# PROC054D_AWR_1_AWR_4_LC_Filtering.net
KiCad netlist of a schematic drawn in Altium Designer
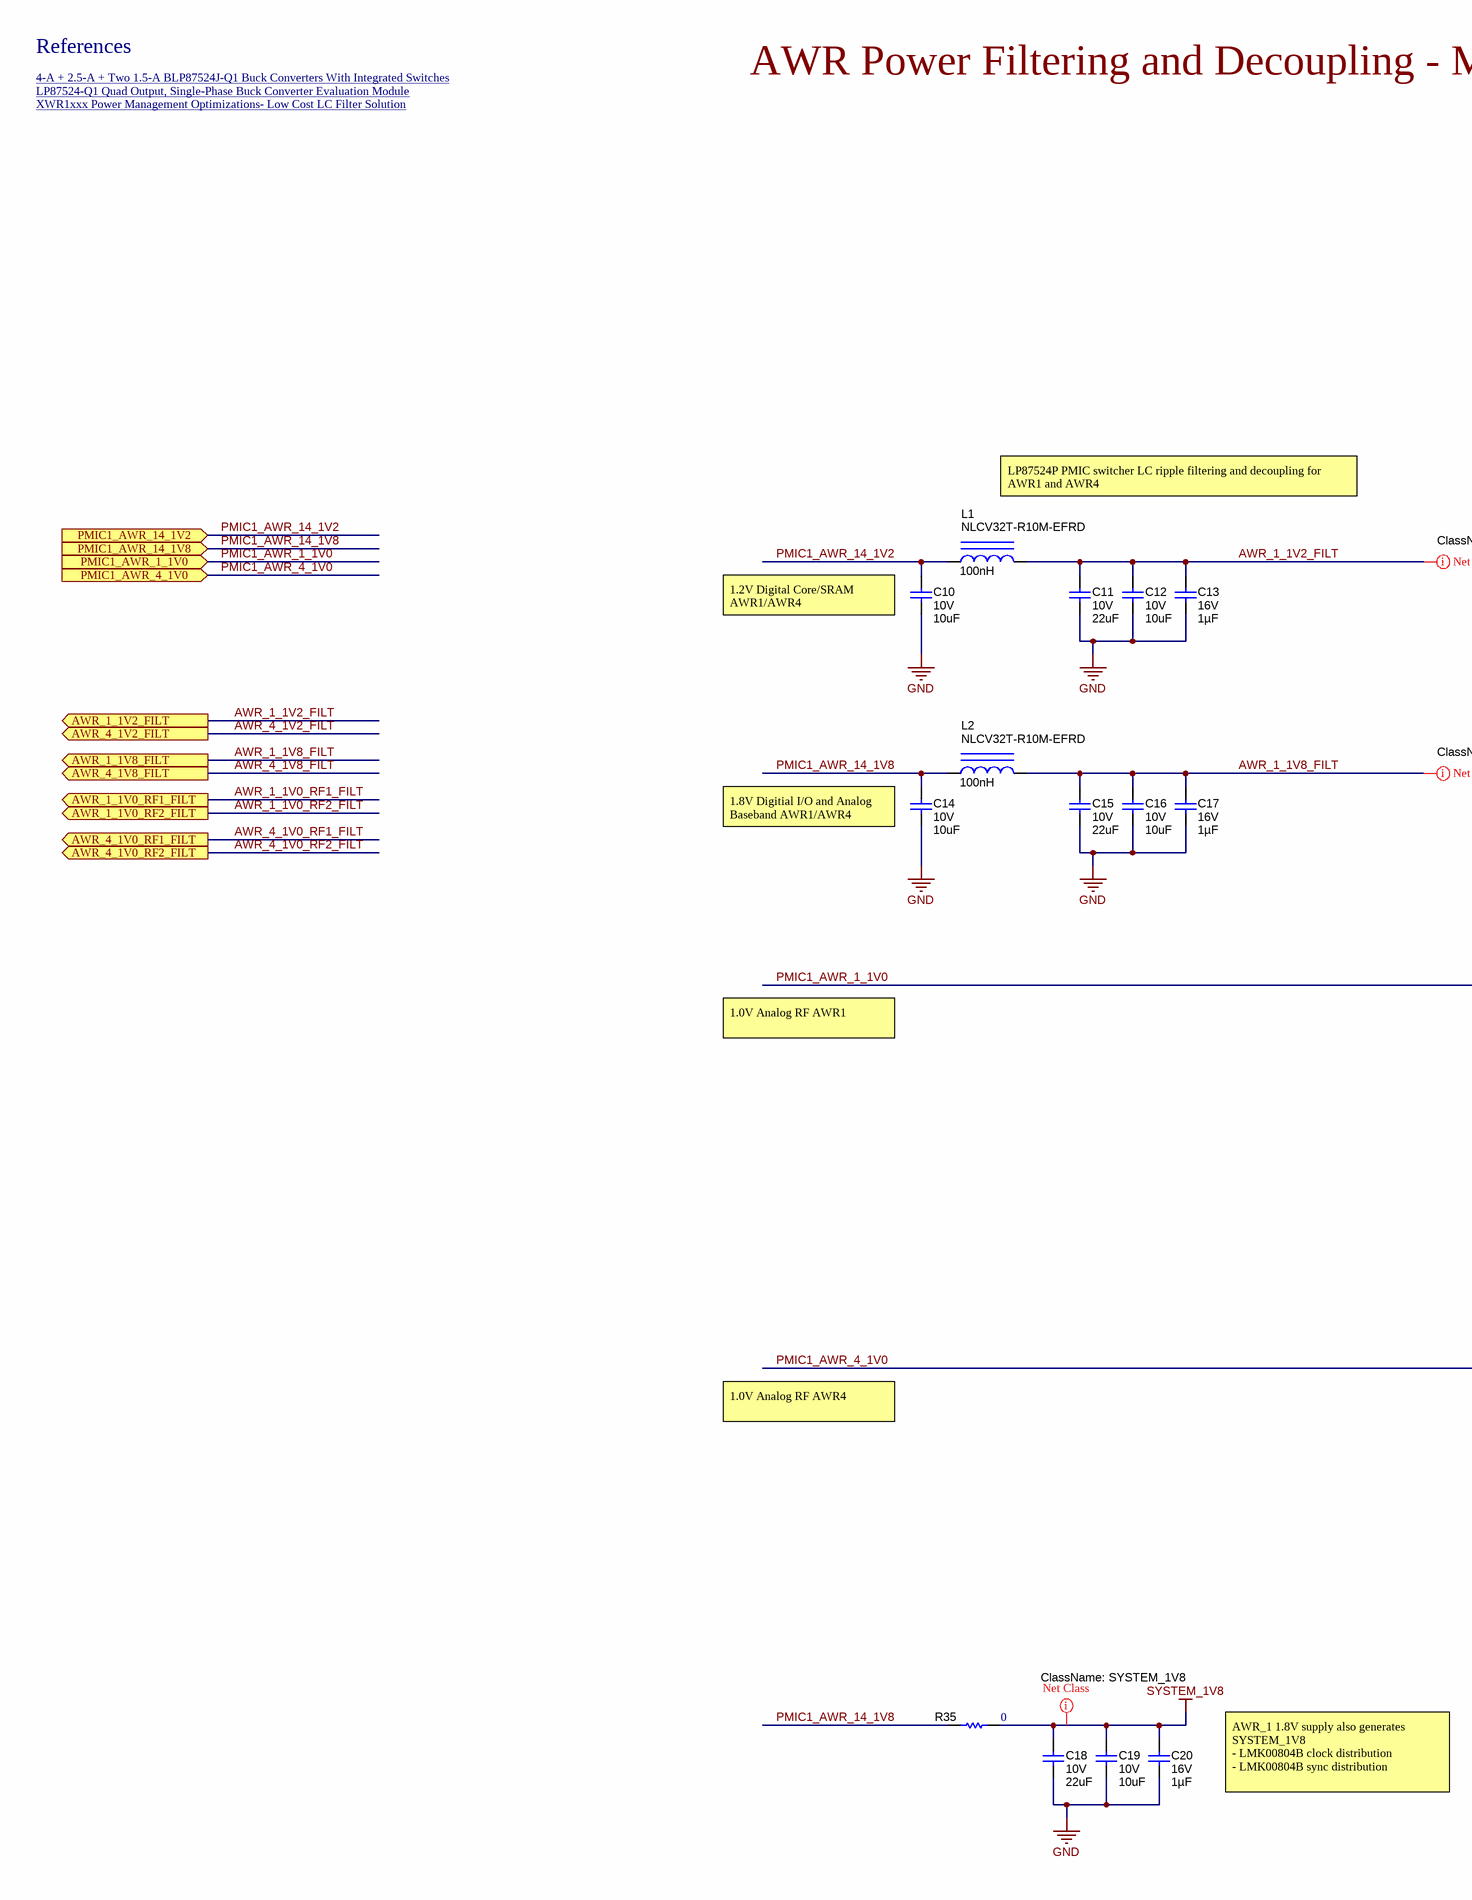
[diagram p0: PROC054D_AWR_1_AWR_4_LC_Filtering.SchDoc, left]
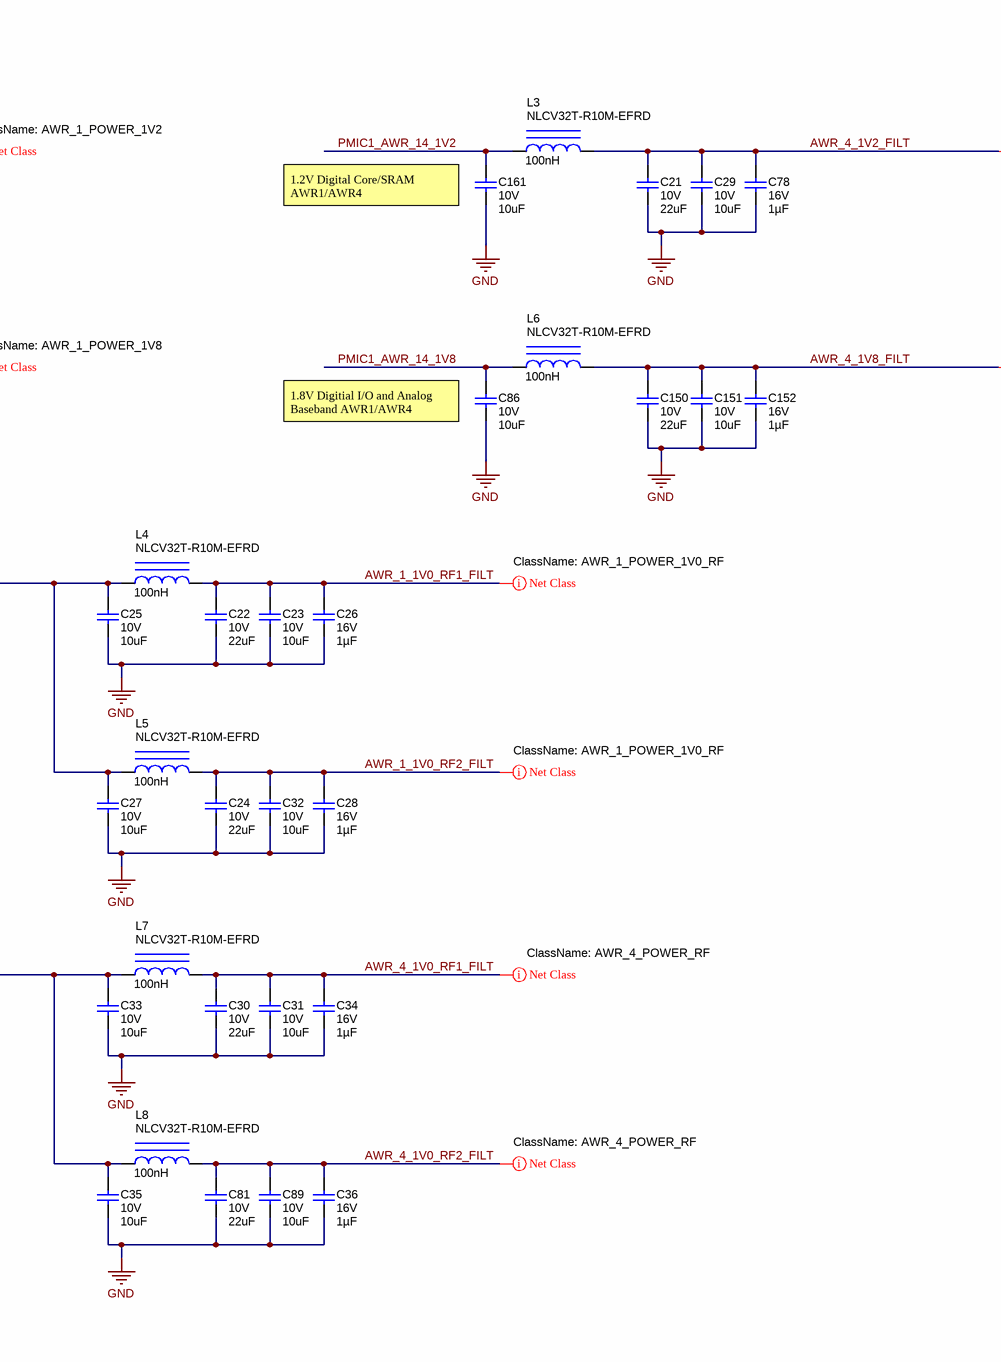
[diagram p1: PROC054D_AWR_1_AWR_4_LC_Filtering.SchDoc, right]

(export (version "E")
  (design (tool "Eeschema 10.0.6"))
  (components
    (comp (ref "C10")
      (value "GCM21BR71A106KE22L")
      (footprint "0805L")
      (description "CAP, CERM, 10 uF, 10 V, +/- 10%, X7R, 0805")
      (fields
        (field (name "MANUFACTURER") "MuRata")
        (field (name "VDC_V") "10V")
        (field (name "VALUEDISPLAYED") "10uF")
        (field (name "PUBLISHER") "Texas Instruments")
      )
      (libsource (lib "Altium Vault - TI") (part "Capacitor"))
    )
    (comp (ref "C11")
      (value "GCM31CR71A226KE02")
      (footprint "1206_180L")
      (description "CAP, CERM, 22 uF, 10 V, +/- 10%, X7R, AEC-Q200 Grade 1, 1206")
      (fields
        (field (name "MANUFACTURER") "MuRata")
        (field (name "VDC_V") "10V")
        (field (name "VALUEDISPLAYED") "22uF")
        (field (name "PUBLISHER") "Texas Instruments")
      )
      (libsource (lib "Altium Vault - TI") (part "CMP-0008811-2"))
    )
    (comp (ref "C12")
      (value "GCM21BR71A106KE22L")
      (footprint "0805L")
      (description "CAP, CERM, 10 uF, 10 V, +/- 10%, X7R, 0805")
      (fields
        (field (name "MANUFACTURER") "MuRata")
        (field (name "VDC_V") "10V")
        (field (name "VALUEDISPLAYED") "10uF")
        (field (name "PUBLISHER") "Texas Instruments")
      )
      (libsource (lib "Altium Vault - TI") (part "Capacitor"))
    )
    (comp (ref "C13")
      (value "GCM188R71C105KA64J")
      (footprint "0603S")
      (description "CAP, CERM, 1 µF, 16 V,+/- 10%, X7R, AEC-Q200 Grade 1, 0603")
      (fields
        (field (name "MANUFACTURER") "MuRata")
        (field (name "VDC_V") "16V")
        (field (name "VALUEDISPLAYED") "1µF")
      )
      (libsource (lib "Altium Vault - TI") (part "Capacitor"))
    )
    (comp (ref "C14")
      (value "GCM21BR71A106KE22L")
      (footprint "0805L")
      (description "CAP, CERM, 10 uF, 10 V, +/- 10%, X7R, 0805")
      (fields
        (field (name "MANUFACTURER") "MuRata")
        (field (name "VDC_V") "10V")
        (field (name "VALUEDISPLAYED") "10uF")
        (field (name "PUBLISHER") "Texas Instruments")
      )
      (libsource (lib "Altium Vault - TI") (part "Capacitor"))
    )
    (comp (ref "C15")
      (value "GCM31CR71A226KE02")
      (footprint "1206_180L")
      (description "CAP, CERM, 22 uF, 10 V, +/- 10%, X7R, AEC-Q200 Grade 1, 1206")
      (fields
        (field (name "MANUFACTURER") "MuRata")
        (field (name "VDC_V") "10V")
        (field (name "VALUEDISPLAYED") "22uF")
        (field (name "PUBLISHER") "Texas Instruments")
      )
      (libsource (lib "Altium Vault - TI") (part "Capacitor"))
    )
    (comp (ref "C16")
      (value "GCM21BR71A106KE22L")
      (footprint "0805L")
      (description "CAP, CERM, 10 uF, 10 V, +/- 10%, X7R, 0805")
      (fields
        (field (name "MANUFACTURER") "MuRata")
        (field (name "VDC_V") "10V")
        (field (name "VALUEDISPLAYED") "10uF")
        (field (name "PUBLISHER") "Texas Instruments")
      )
      (libsource (lib "Altium Vault - TI") (part "Capacitor"))
    )
    (comp (ref "C17")
      (value "GCM188R71C105KA64J")
      (footprint "0603S")
      (description "CAP, CERM, 1 µF, 16 V,+/- 10%, X7R, AEC-Q200 Grade 1, 0603")
      (fields
        (field (name "MANUFACTURER") "MuRata")
        (field (name "VDC_V") "16V")
        (field (name "VALUEDISPLAYED") "1µF")
      )
      (libsource (lib "Altium Vault - TI") (part "Capacitor"))
    )
    (comp (ref "C18")
      (value "GCM31CR71A226KE02")
      (footprint "1206_180L")
      (description "CAP, CERM, 22 uF, 10 V, +/- 10%, X7R, AEC-Q200 Grade 1, 1206")
      (fields
        (field (name "MANUFACTURER") "MuRata")
        (field (name "VDC_V") "10V")
        (field (name "VALUEDISPLAYED") "22uF")
        (field (name "PUBLISHER") "Texas Instruments")
      )
      (libsource (lib "Altium Vault - TI") (part "CMP-0008811-2"))
    )
    (comp (ref "C19")
      (value "GCM21BR71A106KE22L")
      (footprint "0805L")
      (description "CAP, CERM, 10 uF, 10 V, +/- 10%, X7R, 0805")
      (fields
        (field (name "MANUFACTURER") "MuRata")
        (field (name "VDC_V") "10V")
        (field (name "VALUEDISPLAYED") "10uF")
        (field (name "PUBLISHER") "Texas Instruments")
      )
      (libsource (lib "Altium Vault - TI") (part "CMP-0008017-2"))
    )
    (comp (ref "C20")
      (value "GCM188R71C105KA64J")
      (footprint "0603S")
      (description "CAP, CERM, 1 µF, 16 V,+/- 10%, X7R, AEC-Q200 Grade 1, 0603")
      (fields
        (field (name "MANUFACTURER") "MuRata")
        (field (name "VDC_V") "16V")
        (field (name "VALUEDISPLAYED") "1µF")
      )
      (libsource (lib "Altium Vault - TI") (part "CMP-0079154-1"))
    )
    (comp (ref "C21")
      (value "GCM31CR71A226KE02")
      (footprint "1206_180L")
      (description "CAP, CERM, 22 uF, 10 V, +/- 10%, X7R, AEC-Q200 Grade 1, 1206")
      (fields
        (field (name "MANUFACTURER") "MuRata")
        (field (name "VDC_V") "10V")
        (field (name "VALUEDISPLAYED") "22uF")
        (field (name "PUBLISHER") "Texas Instruments")
      )
      (libsource (lib "Altium Vault - TI") (part "Capacitor"))
    )
    (comp (ref "C22")
      (value "GCM31CR71A226KE02")
      (footprint "1206_180L")
      (description "CAP, CERM, 22 uF, 10 V, +/- 10%, X7R, AEC-Q200 Grade 1, 1206")
      (fields
        (field (name "MANUFACTURER") "MuRata")
        (field (name "VDC_V") "10V")
        (field (name "VALUEDISPLAYED") "22uF")
        (field (name "PUBLISHER") "Texas Instruments")
      )
      (libsource (lib "Altium Vault - TI") (part "Capacitor"))
    )
    (comp (ref "C23")
      (value "GCM21BR71A106KE22L")
      (footprint "0805L")
      (description "CAP, CERM, 10 uF, 10 V, +/- 10%, X7R, 0805")
      (fields
        (field (name "MANUFACTURER") "MuRata")
        (field (name "VDC_V") "10V")
        (field (name "VALUEDISPLAYED") "10uF")
        (field (name "PUBLISHER") "Texas Instruments")
      )
      (libsource (lib "Altium Vault - TI") (part "Capacitor"))
    )
    (comp (ref "C24")
      (value "GCM31CR71A226KE02")
      (footprint "1206_180L")
      (description "CAP, CERM, 22 uF, 10 V, +/- 10%, X7R, AEC-Q200 Grade 1, 1206")
      (fields
        (field (name "MANUFACTURER") "MuRata")
        (field (name "VDC_V") "10V")
        (field (name "VALUEDISPLAYED") "22uF")
        (field (name "PUBLISHER") "Texas Instruments")
      )
      (libsource (lib "Altium Vault - TI") (part "Capacitor"))
    )
    (comp (ref "C25")
      (value "GCM21BR71A106KE22L")
      (footprint "0805L")
      (description "CAP, CERM, 10 uF, 10 V, +/- 10%, X7R, 0805")
      (fields
        (field (name "MANUFACTURER") "MuRata")
        (field (name "VDC_V") "10V")
        (field (name "VALUEDISPLAYED") "10uF")
        (field (name "PUBLISHER") "Texas Instruments")
      )
      (libsource (lib "Altium Vault - TI") (part "Capacitor"))
    )
    (comp (ref "C26")
      (value "GCM188R71C105KA64J")
      (footprint "0603S")
      (description "CAP, CERM, 1 µF, 16 V,+/- 10%, X7R, AEC-Q200 Grade 1, 0603")
      (fields
        (field (name "MANUFACTURER") "MuRata")
        (field (name "VDC_V") "16V")
        (field (name "VALUEDISPLAYED") "1µF")
      )
      (libsource (lib "Altium Vault - TI") (part "Capacitor"))
    )
    (comp (ref "C27")
      (value "GCM21BR71A106KE22L")
      (footprint "0805L")
      (description "CAP, CERM, 10 uF, 10 V, +/- 10%, X7R, 0805")
      (fields
        (field (name "MANUFACTURER") "MuRata")
        (field (name "VDC_V") "10V")
        (field (name "VALUEDISPLAYED") "10uF")
        (field (name "PUBLISHER") "Texas Instruments")
      )
      (libsource (lib "Altium Vault - TI") (part "Capacitor"))
    )
    (comp (ref "C28")
      (value "GCM188R71C105KA64J")
      (footprint "0603S")
      (description "CAP, CERM, 1 µF, 16 V,+/- 10%, X7R, AEC-Q200 Grade 1, 0603")
      (fields
        (field (name "MANUFACTURER") "MuRata")
        (field (name "VDC_V") "16V")
        (field (name "VALUEDISPLAYED") "1µF")
      )
      (libsource (lib "Altium Vault - TI") (part "Capacitor"))
    )
    (comp (ref "C29")
      (value "GCM21BR71A106KE22L")
      (footprint "0805L")
      (description "CAP, CERM, 10 uF, 10 V, +/- 10%, X7R, 0805")
      (fields
        (field (name "MANUFACTURER") "MuRata")
        (field (name "VDC_V") "10V")
        (field (name "VALUEDISPLAYED") "10uF")
        (field (name "PUBLISHER") "Texas Instruments")
      )
      (libsource (lib "Altium Vault - TI") (part "Capacitor"))
    )
    (comp (ref "C30")
      (value "GCM31CR71A226KE02")
      (footprint "1206_180L")
      (description "CAP, CERM, 22 uF, 10 V, +/- 10%, X7R, AEC-Q200 Grade 1, 1206")
      (fields
        (field (name "MANUFACTURER") "MuRata")
        (field (name "VDC_V") "10V")
        (field (name "VALUEDISPLAYED") "22uF")
        (field (name "PUBLISHER") "Texas Instruments")
      )
      (libsource (lib "Altium Vault - TI") (part "Capacitor"))
    )
    (comp (ref "C31")
      (value "GCM21BR71A106KE22L")
      (footprint "0805L")
      (description "CAP, CERM, 10 uF, 10 V, +/- 10%, X7R, 0805")
      (fields
        (field (name "MANUFACTURER") "MuRata")
        (field (name "VDC_V") "10V")
        (field (name "VALUEDISPLAYED") "10uF")
        (field (name "PUBLISHER") "Texas Instruments")
      )
      (libsource (lib "Altium Vault - TI") (part "Capacitor"))
    )
    (comp (ref "C32")
      (value "GCM21BR71A106KE22L")
      (footprint "0805L")
      (description "CAP, CERM, 10 uF, 10 V, +/- 10%, X7R, 0805")
      (fields
        (field (name "MANUFACTURER") "MuRata")
        (field (name "VDC_V") "10V")
        (field (name "VALUEDISPLAYED") "10uF")
        (field (name "PUBLISHER") "Texas Instruments")
      )
      (libsource (lib "Altium Vault - TI") (part "Capacitor"))
    )
    (comp (ref "C33")
      (value "GCM21BR71A106KE22L")
      (footprint "0805L")
      (description "CAP, CERM, 10 uF, 10 V, +/- 10%, X7R, 0805")
      (fields
        (field (name "MANUFACTURER") "MuRata")
        (field (name "VDC_V") "10V")
        (field (name "VALUEDISPLAYED") "10uF")
        (field (name "PUBLISHER") "Texas Instruments")
      )
      (libsource (lib "Altium Vault - TI") (part "Capacitor"))
    )
    (comp (ref "C34")
      (value "GCM188R71C105KA64J")
      (footprint "0603S")
      (description "CAP, CERM, 1 µF, 16 V,+/- 10%, X7R, AEC-Q200 Grade 1, 0603")
      (fields
        (field (name "MANUFACTURER") "MuRata")
        (field (name "VDC_V") "16V")
        (field (name "VALUEDISPLAYED") "1µF")
      )
      (libsource (lib "Altium Vault - TI") (part "Capacitor"))
    )
    (comp (ref "C35")
      (value "GCM21BR71A106KE22L")
      (footprint "0805L")
      (description "CAP, CERM, 10 uF, 10 V, +/- 10%, X7R, 0805")
      (fields
        (field (name "MANUFACTURER") "MuRata")
        (field (name "VDC_V") "10V")
        (field (name "VALUEDISPLAYED") "10uF")
        (field (name "PUBLISHER") "Texas Instruments")
      )
      (libsource (lib "Altium Vault - TI") (part "Capacitor"))
    )
    (comp (ref "C36")
      (value "GCM188R71C105KA64J")
      (footprint "0603S")
      (description "CAP, CERM, 1 µF, 16 V,+/- 10%, X7R, AEC-Q200 Grade 1, 0603")
      (fields
        (field (name "MANUFACTURER") "MuRata")
        (field (name "VDC_V") "16V")
        (field (name "VALUEDISPLAYED") "1µF")
      )
      (libsource (lib "Altium Vault - TI") (part "Capacitor"))
    )
    (comp (ref "C78")
      (value "GCM188R71C105KA64J")
      (footprint "0603S")
      (description "CAP, CERM, 1 µF, 16 V,+/- 10%, X7R, AEC-Q200 Grade 1, 0603")
      (fields
        (field (name "MANUFACTURER") "MuRata")
        (field (name "VDC_V") "16V")
        (field (name "VALUEDISPLAYED") "1µF")
      )
      (libsource (lib "Altium Vault - TI") (part "Capacitor"))
    )
    (comp (ref "C81")
      (value "GCM31CR71A226KE02")
      (footprint "1206_180L")
      (description "CAP, CERM, 22 uF, 10 V, +/- 10%, X7R, AEC-Q200 Grade 1, 1206")
      (fields
        (field (name "MANUFACTURER") "MuRata")
        (field (name "VDC_V") "10V")
        (field (name "VALUEDISPLAYED") "22uF")
        (field (name "PUBLISHER") "Texas Instruments")
      )
      (libsource (lib "Altium Vault - TI") (part "Capacitor"))
    )
    (comp (ref "C86")
      (value "GCM21BR71A106KE22L")
      (footprint "0805L")
      (description "CAP, CERM, 10 uF, 10 V, +/- 10%, X7R, 0805")
      (fields
        (field (name "MANUFACTURER") "MuRata")
        (field (name "VDC_V") "10V")
        (field (name "VALUEDISPLAYED") "10uF")
        (field (name "PUBLISHER") "Texas Instruments")
      )
      (libsource (lib "Altium Vault - TI") (part "Capacitor"))
    )
    (comp (ref "C89")
      (value "GCM21BR71A106KE22L")
      (footprint "0805L")
      (description "CAP, CERM, 10 uF, 10 V, +/- 10%, X7R, 0805")
      (fields
        (field (name "MANUFACTURER") "MuRata")
        (field (name "VDC_V") "10V")
        (field (name "VALUEDISPLAYED") "10uF")
        (field (name "PUBLISHER") "Texas Instruments")
      )
      (libsource (lib "Altium Vault - TI") (part "Capacitor"))
    )
    (comp (ref "C150")
      (value "GCM31CR71A226KE02")
      (footprint "1206_180L")
      (description "CAP, CERM, 22 uF, 10 V, +/- 10%, X7R, AEC-Q200 Grade 1, 1206")
      (fields
        (field (name "MANUFACTURER") "MuRata")
        (field (name "VDC_V") "10V")
        (field (name "VALUEDISPLAYED") "22uF")
        (field (name "PUBLISHER") "Texas Instruments")
      )
      (libsource (lib "Altium Vault - TI") (part "Capacitor"))
    )
    (comp (ref "C151")
      (value "GCM21BR71A106KE22L")
      (footprint "0805L")
      (description "CAP, CERM, 10 uF, 10 V, +/- 10%, X7R, 0805")
      (fields
        (field (name "MANUFACTURER") "MuRata")
        (field (name "VDC_V") "10V")
        (field (name "VALUEDISPLAYED") "10uF")
        (field (name "PUBLISHER") "Texas Instruments")
      )
      (libsource (lib "Altium Vault - TI") (part "Capacitor"))
    )
    (comp (ref "C152")
      (value "GCM188R71C105KA64J")
      (footprint "0603S")
      (description "CAP, CERM, 1 µF, 16 V,+/- 10%, X7R, AEC-Q200 Grade 1, 0603")
      (fields
        (field (name "MANUFACTURER") "MuRata")
        (field (name "VDC_V") "16V")
        (field (name "VALUEDISPLAYED") "1µF")
      )
      (libsource (lib "Altium Vault - TI") (part "Capacitor"))
    )
    (comp (ref "C161")
      (value "GCM21BR71A106KE22L")
      (footprint "0805L")
      (description "CAP, CERM, 10 uF, 10 V, +/- 10%, X7R, 0805")
      (fields
        (field (name "MANUFACTURER") "MuRata")
        (field (name "VDC_V") "10V")
        (field (name "VALUEDISPLAYED") "10uF")
        (field (name "PUBLISHER") "Texas Instruments")
      )
      (libsource (lib "Altium Vault - TI") (part "Capacitor"))
    )
    (comp (ref "L1")
      (value "NLCV32T-R10M-EFRD")
      (footprint "NLCV32")
      (description "Inductor, Wirewound, Ferrite, 100 nH, 2.85 A, 0.024 ohm, AEC-Q200 Grade 1, SMD")
      (fields
        (field (name "MANUFACTURER") "TDK")
        (field (name "PARTNUMBER") "NLCV32T-R10M-EFRD")
        (field (name "VALUEDISPLAYED") "100nH")
      )
      (libsource (lib "Altium Vault - TI") (part "CMP-0083745-1"))
    )
    (comp (ref "L2")
      (value "NLCV32T-R10M-EFRD")
      (footprint "NLCV32")
      (description "Inductor, Wirewound, Ferrite, 100 nH, 2.85 A, 0.024 ohm, AEC-Q200 Grade 1, SMD")
      (fields
        (field (name "MANUFACTURER") "TDK")
        (field (name "PARTNUMBER") "NLCV32T-R10M-EFRD")
        (field (name "VALUEDISPLAYED") "100nH")
      )
      (libsource (lib "Altium Vault - TI") (part "CMP-0083745-1"))
    )
    (comp (ref "L3")
      (value "NLCV32T-R10M-EFRD")
      (footprint "NLCV32")
      (description "Inductor, Wirewound, Ferrite, 100 nH, 2.85 A, 0.024 ohm, AEC-Q200 Grade 1, SMD")
      (fields
        (field (name "MANUFACTURER") "TDK")
        (field (name "PARTNUMBER") "NLCV32T-R10M-EFRD")
        (field (name "VALUEDISPLAYED") "100nH")
      )
      (libsource (lib "Altium Vault - TI") (part "CMP-0083745-1"))
    )
    (comp (ref "L4")
      (value "NLCV32T-R10M-EFRD")
      (footprint "NLCV32")
      (description "Inductor, Wirewound, Ferrite, 100 nH, 2.85 A, 0.024 ohm, AEC-Q200 Grade 1, SMD")
      (fields
        (field (name "MANUFACTURER") "TDK")
        (field (name "PARTNUMBER") "NLCV32T-R10M-EFRD")
        (field (name "VALUEDISPLAYED") "100nH")
      )
      (libsource (lib "Altium Vault - TI") (part "CMP-0083745-1"))
    )
    (comp (ref "L5")
      (value "NLCV32T-R10M-EFRD")
      (footprint "NLCV32")
      (description "Inductor, Wirewound, Ferrite, 100 nH, 2.85 A, 0.024 ohm, AEC-Q200 Grade 1, SMD")
      (fields
        (field (name "MANUFACTURER") "TDK")
        (field (name "PARTNUMBER") "NLCV32T-R10M-EFRD")
        (field (name "VALUEDISPLAYED") "100nH")
      )
      (libsource (lib "Altium Vault - TI") (part "CMP-0083745-1"))
    )
    (comp (ref "L6")
      (value "NLCV32T-R10M-EFRD")
      (footprint "NLCV32")
      (description "Inductor, Wirewound, Ferrite, 100 nH, 2.85 A, 0.024 ohm, AEC-Q200 Grade 1, SMD")
      (fields
        (field (name "MANUFACTURER") "TDK")
        (field (name "PARTNUMBER") "NLCV32T-R10M-EFRD")
        (field (name "VALUEDISPLAYED") "100nH")
      )
      (libsource (lib "Altium Vault - TI") (part "CMP-0083745-1"))
    )
    (comp (ref "L7")
      (value "NLCV32T-R10M-EFRD")
      (footprint "NLCV32")
      (description "Inductor, Wirewound, Ferrite, 100 nH, 2.85 A, 0.024 ohm, AEC-Q200 Grade 1, SMD")
      (fields
        (field (name "MANUFACTURER") "TDK")
        (field (name "PARTNUMBER") "NLCV32T-R10M-EFRD")
        (field (name "VALUEDISPLAYED") "100nH")
      )
      (libsource (lib "Altium Vault - TI") (part "CMP-0083745-1"))
    )
    (comp (ref "L8")
      (value "NLCV32T-R10M-EFRD")
      (footprint "NLCV32")
      (description "Inductor, Wirewound, Ferrite, 100 nH, 2.85 A, 0.024 ohm, AEC-Q200 Grade 1, SMD")
      (fields
        (field (name "MANUFACTURER") "TDK")
        (field (name "PARTNUMBER") "NLCV32T-R10M-EFRD")
        (field (name "VALUEDISPLAYED") "100nH")
      )
      (libsource (lib "Altium Vault - TI") (part "CMP-0083745-1"))
    )
    (comp (ref "R35")
      (value "PMR10EZPJ000")
      (footprint "0805_HV")
      (description "RES, 0, 0%,  W, AEC-Q200 Grade 0, 0805")
      (fields (field (name "MANUFACTURER") "Rohm") (field (name "VALUEDISPLAYED") "0"))
      (libsource (lib "Altium Vault - TI") (part "Resistor"))
    )
  )
  (nets
    (net (code "1") (name "/AWR_1_1V0_RF1_FILT") (class "Default")
      (node (ref "C22") (pin "1") (pinfunction "1_1") (pintype "passive"))
      (node (ref "C23") (pin "1") (pinfunction "1_1") (pintype "passive"))
      (node (ref "C26") (pin "1") (pinfunction "1_1") (pintype "passive"))
      (node (ref "L4") (pin "2") (pinfunction "2_2") (pintype "passive"))
    )
    (net (code "2") (name "/AWR_1_1V0_RF2_FILT") (class "Default")
      (node (ref "C24") (pin "1") (pinfunction "1_1") (pintype "passive"))
      (node (ref "C28") (pin "1") (pinfunction "1_1") (pintype "passive"))
      (node (ref "C32") (pin "1") (pinfunction "1_1") (pintype "passive"))
      (node (ref "L5") (pin "2") (pinfunction "2_2") (pintype "passive"))
    )
    (net (code "3") (name "/AWR_1_1V2_FILT") (class "Default")
      (node (ref "C11") (pin "1") (pinfunction "1_1") (pintype "passive"))
      (node (ref "C12") (pin "1") (pinfunction "1_1") (pintype "passive"))
      (node (ref "C13") (pin "1") (pinfunction "1_1") (pintype "passive"))
      (node (ref "L1") (pin "2") (pinfunction "2_2") (pintype "passive"))
    )
    (net (code "4") (name "/AWR_1_1V8_FILT") (class "Default")
      (node (ref "C15") (pin "1") (pinfunction "1_1") (pintype "passive"))
      (node (ref "C16") (pin "1") (pinfunction "1_1") (pintype "passive"))
      (node (ref "C17") (pin "1") (pinfunction "1_1") (pintype "passive"))
      (node (ref "L2") (pin "2") (pinfunction "2_2") (pintype "passive"))
    )
    (net (code "5") (name "/AWR_4_1V0_RF1_FILT") (class "Default")
      (node (ref "C30") (pin "1") (pinfunction "1_1") (pintype "passive"))
      (node (ref "C31") (pin "1") (pinfunction "1_1") (pintype "passive"))
      (node (ref "C34") (pin "1") (pinfunction "1_1") (pintype "passive"))
      (node (ref "L7") (pin "2") (pinfunction "2_2") (pintype "passive"))
    )
    (net (code "6") (name "/AWR_4_1V0_RF2_FILT") (class "Default")
      (node (ref "C36") (pin "1") (pinfunction "1_1") (pintype "passive"))
      (node (ref "C81") (pin "1") (pinfunction "1_1") (pintype "passive"))
      (node (ref "C89") (pin "1") (pinfunction "1_1") (pintype "passive"))
      (node (ref "L8") (pin "2") (pinfunction "2_2") (pintype "passive"))
    )
    (net (code "7") (name "/AWR_4_1V2_FILT") (class "Default")
      (node (ref "C21") (pin "1") (pinfunction "1_1") (pintype "passive"))
      (node (ref "C29") (pin "1") (pinfunction "1_1") (pintype "passive"))
      (node (ref "C78") (pin "1") (pinfunction "1_1") (pintype "passive"))
      (node (ref "L3") (pin "2") (pinfunction "2_2") (pintype "passive"))
    )
    (net (code "8") (name "/AWR_4_1V8_FILT") (class "Default")
      (node (ref "C150") (pin "1") (pinfunction "1_1") (pintype "passive"))
      (node (ref "C151") (pin "1") (pinfunction "1_1") (pintype "passive"))
      (node (ref "C152") (pin "1") (pinfunction "1_1") (pintype "passive"))
      (node (ref "L6") (pin "2") (pinfunction "2_2") (pintype "passive"))
    )
    (net (code "9") (name "/PMIC1_AWR_1_1V0") (class "Default")
      (node (ref "C25") (pin "1") (pinfunction "1_1") (pintype "passive"))
      (node (ref "C27") (pin "1") (pinfunction "1_1") (pintype "passive"))
      (node (ref "L4") (pin "1") (pinfunction "1_1") (pintype "passive"))
      (node (ref "L5") (pin "1") (pinfunction "1_1") (pintype "passive"))
    )
    (net (code "10") (name "/PMIC1_AWR_4_1V0") (class "Default")
      (node (ref "C33") (pin "1") (pinfunction "1_1") (pintype "passive"))
      (node (ref "C35") (pin "1") (pinfunction "1_1") (pintype "passive"))
      (node (ref "L7") (pin "1") (pinfunction "1_1") (pintype "passive"))
      (node (ref "L8") (pin "1") (pinfunction "1_1") (pintype "passive"))
    )
    (net (code "11") (name "/PMIC1_AWR_14_1V2") (class "Default")
      (node (ref "C10") (pin "1") (pinfunction "1_1") (pintype "passive"))
      (node (ref "C161") (pin "1") (pinfunction "1_1") (pintype "passive"))
      (node (ref "L1") (pin "1") (pinfunction "1_1") (pintype "passive"))
      (node (ref "L3") (pin "1") (pinfunction "1_1") (pintype "passive"))
    )
    (net (code "12") (name "/PMIC1_AWR_14_1V8") (class "Default")
      (node (ref "C14") (pin "1") (pinfunction "1_1") (pintype "passive"))
      (node (ref "C86") (pin "1") (pinfunction "1_1") (pintype "passive"))
      (node (ref "L2") (pin "1") (pinfunction "1_1") (pintype "passive"))
      (node (ref "L6") (pin "1") (pinfunction "1_1") (pintype "passive"))
      (node (ref "R35") (pin "1") (pinfunction "1_1") (pintype "passive"))
    )
    (net (code "13") (name "GND") (class "Default")
      (node (ref "C10") (pin "2") (pinfunction "2_2") (pintype "passive"))
      (node (ref "C11") (pin "2") (pinfunction "2_2") (pintype "passive"))
      (node (ref "C12") (pin "2") (pinfunction "2_2") (pintype "passive"))
      (node (ref "C13") (pin "2") (pinfunction "2_2") (pintype "passive"))
      (node (ref "C14") (pin "2") (pinfunction "2_2") (pintype "passive"))
      (node (ref "C15") (pin "2") (pinfunction "2_2") (pintype "passive"))
      (node (ref "C150") (pin "2") (pinfunction "2_2") (pintype "passive"))
      (node (ref "C151") (pin "2") (pinfunction "2_2") (pintype "passive"))
      (node (ref "C152") (pin "2") (pinfunction "2_2") (pintype "passive"))
      (node (ref "C16") (pin "2") (pinfunction "2_2") (pintype "passive"))
      (node (ref "C161") (pin "2") (pinfunction "2_2") (pintype "passive"))
      (node (ref "C17") (pin "2") (pinfunction "2_2") (pintype "passive"))
      (node (ref "C18") (pin "2") (pinfunction "2_2") (pintype "passive"))
      (node (ref "C19") (pin "2") (pinfunction "2_2") (pintype "passive"))
      (node (ref "C20") (pin "2") (pinfunction "2_2") (pintype "passive"))
      (node (ref "C21") (pin "2") (pinfunction "2_2") (pintype "passive"))
      (node (ref "C22") (pin "2") (pinfunction "2_2") (pintype "passive"))
      (node (ref "C23") (pin "2") (pinfunction "2_2") (pintype "passive"))
      (node (ref "C24") (pin "2") (pinfunction "2_2") (pintype "passive"))
      (node (ref "C25") (pin "2") (pinfunction "2_2") (pintype "passive"))
      (node (ref "C26") (pin "2") (pinfunction "2_2") (pintype "passive"))
      (node (ref "C27") (pin "2") (pinfunction "2_2") (pintype "passive"))
      (node (ref "C28") (pin "2") (pinfunction "2_2") (pintype "passive"))
      (node (ref "C29") (pin "2") (pinfunction "2_2") (pintype "passive"))
      (node (ref "C30") (pin "2") (pinfunction "2_2") (pintype "passive"))
      (node (ref "C31") (pin "2") (pinfunction "2_2") (pintype "passive"))
      (node (ref "C32") (pin "2") (pinfunction "2_2") (pintype "passive"))
      (node (ref "C33") (pin "2") (pinfunction "2_2") (pintype "passive"))
      (node (ref "C34") (pin "2") (pinfunction "2_2") (pintype "passive"))
      (node (ref "C35") (pin "2") (pinfunction "2_2") (pintype "passive"))
      (node (ref "C36") (pin "2") (pinfunction "2_2") (pintype "passive"))
      (node (ref "C78") (pin "2") (pinfunction "2_2") (pintype "passive"))
      (node (ref "C81") (pin "2") (pinfunction "2_2") (pintype "passive"))
      (node (ref "C86") (pin "2") (pinfunction "2_2") (pintype "passive"))
      (node (ref "C89") (pin "2") (pinfunction "2_2") (pintype "passive"))
    )
    (net (code "14") (name "SYSTEM_1V8") (class "Default")
      (node (ref "C18") (pin "1") (pinfunction "1_1") (pintype "passive"))
      (node (ref "C19") (pin "1") (pinfunction "1_1") (pintype "passive"))
      (node (ref "C20") (pin "1") (pinfunction "1_1") (pintype "passive"))
      (node (ref "R35") (pin "2") (pinfunction "2_2") (pintype "passive"))
    )
  )
)
